# fsh.net
KiCad netlist of a schematic drawn in Altium Designer
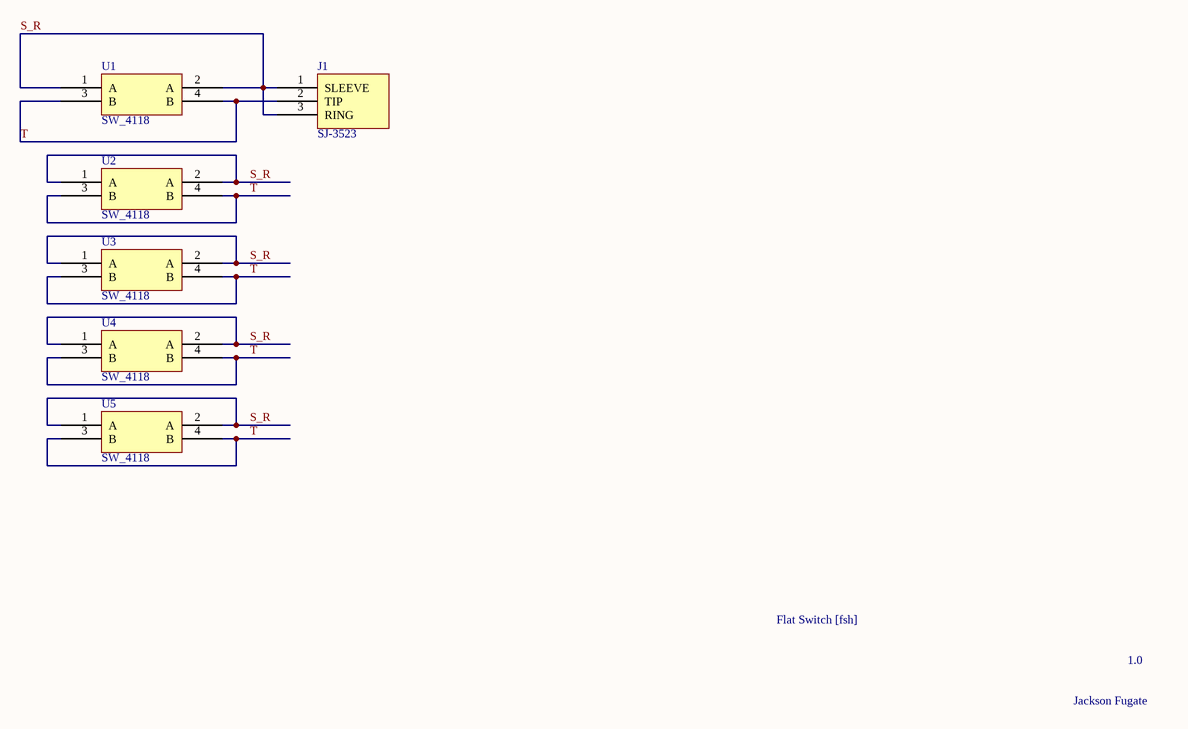
[diagram p0: fsh.SchDoc]

(export (version "E")
  (design (tool "Eeschema 10.0.6"))
  (components
    (comp (ref "J1")
      (value "SJ-3523")
      (footprint "SJ-352X")
      (libsource (lib "JF_master_lib") (part "SJ-3523"))
    )
    (comp (ref "U1")
      (value "SW_4118")
      (footprint "master_pcb:SW_4118_FLAT")
      (libsource (lib "JF_master_lib") (part "SW_4118"))
    )
    (comp (ref "U2")
      (value "SW_4118")
      (footprint "master_pcb:SW_4118_FLAT")
      (libsource (lib "JF_master_lib") (part "SW_4118"))
    )
    (comp (ref "U3")
      (value "SW_4118")
      (footprint "master_pcb:SW_4118_FLAT")
      (libsource (lib "JF_master_lib") (part "SW_4118"))
    )
    (comp (ref "U4")
      (value "SW_4118")
      (footprint "master_pcb:SW_4118_FLAT")
      (libsource (lib "JF_master_lib") (part "SW_4118"))
    )
    (comp (ref "U5")
      (value "SW_4118")
      (footprint "master_pcb:SW_4118_FLAT")
      (libsource (lib "JF_master_lib") (part "SW_4118"))
    )
  )
  (nets
    (net (code "1") (name "/S_R") (class "Default")
      (node (ref "J1") (pin "1") (pinfunction "SLEEVE_1") (pintype "passive"))
      (node (ref "J1") (pin "3") (pinfunction "RING_3") (pintype "passive"))
      (node (ref "U1") (pin "1") (pinfunction "A_1") (pintype "passive"))
      (node (ref "U1") (pin "2") (pinfunction "A_2") (pintype "passive"))
      (node (ref "U2") (pin "1") (pinfunction "A_1") (pintype "passive"))
      (node (ref "U2") (pin "2") (pinfunction "A_2") (pintype "passive"))
      (node (ref "U3") (pin "1") (pinfunction "A_1") (pintype "passive"))
      (node (ref "U3") (pin "2") (pinfunction "A_2") (pintype "passive"))
      (node (ref "U4") (pin "1") (pinfunction "A_1") (pintype "passive"))
      (node (ref "U4") (pin "2") (pinfunction "A_2") (pintype "passive"))
      (node (ref "U5") (pin "1") (pinfunction "A_1") (pintype "passive"))
      (node (ref "U5") (pin "2") (pinfunction "A_2") (pintype "passive"))
    )
    (net (code "2") (name "/T") (class "Default")
      (node (ref "J1") (pin "2") (pinfunction "TIP_2") (pintype "passive"))
      (node (ref "U1") (pin "3") (pinfunction "B_3") (pintype "passive"))
      (node (ref "U1") (pin "4") (pinfunction "B_4") (pintype "passive"))
      (node (ref "U2") (pin "3") (pinfunction "B_3") (pintype "passive"))
      (node (ref "U2") (pin "4") (pinfunction "B_4") (pintype "passive"))
      (node (ref "U3") (pin "3") (pinfunction "B_3") (pintype "passive"))
      (node (ref "U3") (pin "4") (pinfunction "B_4") (pintype "passive"))
      (node (ref "U4") (pin "3") (pinfunction "B_3") (pintype "passive"))
      (node (ref "U4") (pin "4") (pinfunction "B_4") (pintype "passive"))
      (node (ref "U5") (pin "3") (pinfunction "B_3") (pintype "passive"))
      (node (ref "U5") (pin "4") (pinfunction "B_4") (pintype "passive"))
    )
  )
)
